# CV060_IO.net
KiCad netlist of a schematic drawn in Altium Designer
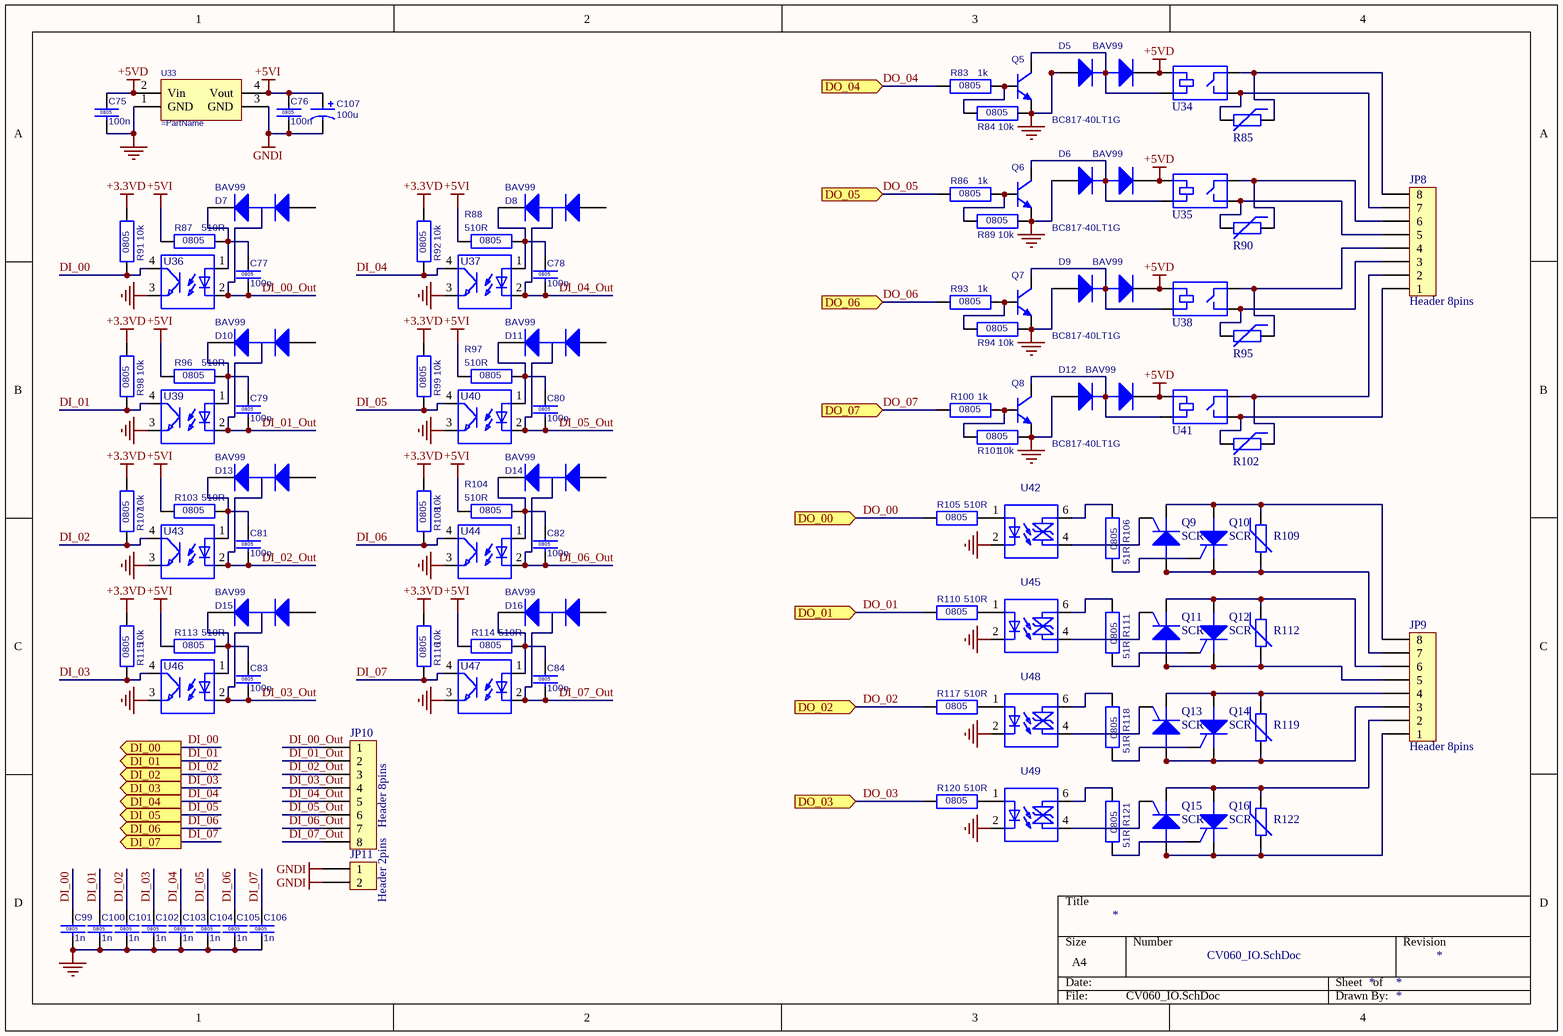
[diagram p0: CV060_IO.SchDoc]

(export (version "E")
  (design (tool "Eeschema 10.0.6"))
  (components
    (comp (ref "C75")
      (value "100n")
      (footprint "RC0805")
      (description "Chip capacitor, 20p")
      (fields
        (field (name "VOLTAGE") "50V")
        (field (name "MANUFACTURER") "KEMET, YAGEO")
        (field (name "CASE") "0805")
      )
      (libsource (lib "Aldiva_Altium_Library") (part "Capacitor_nonpolar_case"))
    )
    (comp (ref "C76")
      (value "100n")
      (footprint "RC0805")
      (description "Chip capacitor, 20p")
      (fields
        (field (name "VOLTAGE") "50V")
        (field (name "MANUFACTURER") "KEMET, YAGEO")
        (field (name "CASE") "0805")
      )
      (libsource (lib "Aldiva_Altium_Library") (part "Capacitor_nonpolar_case"))
    )
    (comp (ref "C77")
      (value "100n")
      (footprint "RC0805")
      (description "Chip capacitor, 20p")
      (fields
        (field (name "VOLTAGE") "50V")
        (field (name "MANUFACTURER") "KEMET, YAGEO")
        (field (name "CASE") "0805")
      )
      (libsource (lib "Aldiva_Altium_Library") (part "Capacitor_nonpolar_case"))
    )
    (comp (ref "C78")
      (value "100n")
      (footprint "RC0805")
      (description "Chip capacitor, 20p")
      (fields
        (field (name "VOLTAGE") "50V")
        (field (name "MANUFACTURER") "KEMET, YAGEO")
        (field (name "CASE") "0805")
      )
      (libsource (lib "Aldiva_Altium_Library") (part "Capacitor_nonpolar_case"))
    )
    (comp (ref "C79")
      (value "100n")
      (footprint "RC0805")
      (description "Chip capacitor, 20p")
      (fields
        (field (name "VOLTAGE") "50V")
        (field (name "MANUFACTURER") "KEMET, YAGEO")
        (field (name "CASE") "0805")
      )
      (libsource (lib "Aldiva_Altium_Library") (part "Capacitor_nonpolar_case"))
    )
    (comp (ref "C80")
      (value "100n")
      (footprint "RC0805")
      (description "Chip capacitor, 20p")
      (fields
        (field (name "VOLTAGE") "50V")
        (field (name "MANUFACTURER") "KEMET, YAGEO")
        (field (name "CASE") "0805")
      )
      (libsource (lib "Aldiva_Altium_Library") (part "Capacitor_nonpolar_case"))
    )
    (comp (ref "C81")
      (value "100n")
      (footprint "RC0805")
      (description "Chip capacitor, 20p")
      (fields
        (field (name "VOLTAGE") "50V")
        (field (name "MANUFACTURER") "KEMET, YAGEO")
        (field (name "CASE") "0805")
      )
      (libsource (lib "Aldiva_Altium_Library") (part "Capacitor_nonpolar_case"))
    )
    (comp (ref "C82")
      (value "100n")
      (footprint "RC0805")
      (description "Chip capacitor, 20p")
      (fields
        (field (name "VOLTAGE") "50V")
        (field (name "MANUFACTURER") "KEMET, YAGEO")
        (field (name "CASE") "0805")
      )
      (libsource (lib "Aldiva_Altium_Library") (part "Capacitor_nonpolar_case"))
    )
    (comp (ref "C83")
      (value "100n")
      (footprint "RC0805")
      (description "Chip capacitor, 20p")
      (fields
        (field (name "VOLTAGE") "50V")
        (field (name "MANUFACTURER") "KEMET, YAGEO")
        (field (name "CASE") "0805")
      )
      (libsource (lib "Aldiva_Altium_Library") (part "Capacitor_nonpolar_case"))
    )
    (comp (ref "C84")
      (value "100n")
      (footprint "RC0805")
      (description "Chip capacitor, 20p")
      (fields
        (field (name "VOLTAGE") "50V")
        (field (name "MANUFACTURER") "KEMET, YAGEO")
        (field (name "CASE") "0805")
      )
      (libsource (lib "Aldiva_Altium_Library") (part "Capacitor_nonpolar_case"))
    )
    (comp (ref "C99")
      (value "1n")
      (footprint "RC0805")
      (description "Chip capacitor, 20p")
      (fields
        (field (name "VOLTAGE") "50V")
        (field (name "MANUFACTURER") "KEMET, YAGEO")
        (field (name "CASE") "0805")
      )
      (libsource (lib "Aldiva_Altium_Library") (part "Capacitor_nonpolar_case"))
    )
    (comp (ref "C100")
      (value "1n")
      (footprint "RC0805")
      (description "Chip capacitor, 20p")
      (fields
        (field (name "VOLTAGE") "50V")
        (field (name "MANUFACTURER") "KEMET, YAGEO")
        (field (name "CASE") "0805")
      )
      (libsource (lib "Aldiva_Altium_Library") (part "Capacitor_nonpolar_case"))
    )
    (comp (ref "C101")
      (value "1n")
      (footprint "RC0805")
      (description "Chip capacitor, 20p")
      (fields
        (field (name "VOLTAGE") "50V")
        (field (name "MANUFACTURER") "KEMET, YAGEO")
        (field (name "CASE") "0805")
      )
      (libsource (lib "Aldiva_Altium_Library") (part "Capacitor_nonpolar_case"))
    )
    (comp (ref "C102")
      (value "1n")
      (footprint "RC0805")
      (description "Chip capacitor, 20p")
      (fields
        (field (name "VOLTAGE") "50V")
        (field (name "MANUFACTURER") "KEMET, YAGEO")
        (field (name "CASE") "0805")
      )
      (libsource (lib "Aldiva_Altium_Library") (part "Capacitor_nonpolar_case"))
    )
    (comp (ref "C103")
      (value "1n")
      (footprint "RC0805")
      (description "Chip capacitor, 20p")
      (fields
        (field (name "VOLTAGE") "50V")
        (field (name "MANUFACTURER") "KEMET, YAGEO")
        (field (name "CASE") "0805")
      )
      (libsource (lib "Aldiva_Altium_Library") (part "Capacitor_nonpolar_case"))
    )
    (comp (ref "C104")
      (value "1n")
      (footprint "RC0805")
      (description "Chip capacitor, 20p")
      (fields
        (field (name "VOLTAGE") "50V")
        (field (name "MANUFACTURER") "KEMET, YAGEO")
        (field (name "CASE") "0805")
      )
      (libsource (lib "Aldiva_Altium_Library") (part "Capacitor_nonpolar_case"))
    )
    (comp (ref "C105")
      (value "1n")
      (footprint "RC0805")
      (description "Chip capacitor, 20p")
      (fields
        (field (name "VOLTAGE") "50V")
        (field (name "MANUFACTURER") "KEMET, YAGEO")
        (field (name "CASE") "0805")
      )
      (libsource (lib "Aldiva_Altium_Library") (part "Capacitor_nonpolar_case"))
    )
    (comp (ref "C106")
      (value "1n")
      (footprint "RC0805")
      (description "Chip capacitor, 20p")
      (fields
        (field (name "VOLTAGE") "50V")
        (field (name "MANUFACTURER") "KEMET, YAGEO")
        (field (name "CASE") "0805")
      )
      (libsource (lib "Aldiva_Altium_Library") (part "Capacitor_nonpolar_case"))
    )
    (comp (ref "C107")
      (value "100u")
      (footprint "CEH12.5D5P2.5")
      (description "Electrolytic capacitor")
      (fields (field (name "PART NUMBER") "CEH12.5D5P2.5M-16V-100U") (field (name "VOLTAGE") "16V"))
      (libsource (lib "Aldiva_Altium_Library") (part "Capacitor_polar"))
    )
    (comp (ref "D5")
      (value "BAV99")
      (footprint "SOT23-3")
      (description "Dual small signal diode")
      (fields
        (field (name "MANUFACTURER") "Fairchild")
        (field (name "PART NUMBER") "BAV99")
        (field (name "VOLTAGE") "70V")
      )
      (libsource (lib "Aldiva_Altium_Library") (part "BAV99"))
    )
    (comp (ref "D6")
      (value "BAV99")
      (footprint "SOT23-3")
      (description "Dual small signal diode")
      (fields
        (field (name "MANUFACTURER") "Fairchild")
        (field (name "PART NUMBER") "BAV99")
        (field (name "VOLTAGE") "70V")
      )
      (libsource (lib "Aldiva_Altium_Library") (part "BAV99"))
    )
    (comp (ref "D7")
      (value "BAV99")
      (footprint "SOT23-3")
      (description "Dual small signal diode")
      (fields
        (field (name "MANUFACTURER") "Fairchild")
        (field (name "PART NUMBER") "BAV99")
        (field (name "VOLTAGE") "70V")
      )
      (libsource (lib "Aldiva_Altium_Library") (part "BAV99"))
    )
    (comp (ref "D8")
      (value "BAV99")
      (footprint "SOT23-3")
      (description "Dual small signal diode")
      (fields
        (field (name "MANUFACTURER") "Fairchild")
        (field (name "PART NUMBER") "BAV99")
        (field (name "VOLTAGE") "70V")
      )
      (libsource (lib "Aldiva_Altium_Library") (part "BAV99"))
    )
    (comp (ref "D9")
      (value "BAV99")
      (footprint "SOT23-3")
      (description "Dual small signal diode")
      (fields
        (field (name "MANUFACTURER") "Fairchild")
        (field (name "PART NUMBER") "BAV99")
        (field (name "VOLTAGE") "70V")
      )
      (libsource (lib "Aldiva_Altium_Library") (part "BAV99"))
    )
    (comp (ref "D10")
      (value "BAV99")
      (footprint "SOT23-3")
      (description "Dual small signal diode")
      (fields
        (field (name "MANUFACTURER") "Fairchild")
        (field (name "PART NUMBER") "BAV99")
        (field (name "VOLTAGE") "70V")
      )
      (libsource (lib "Aldiva_Altium_Library") (part "BAV99"))
    )
    (comp (ref "D11")
      (value "BAV99")
      (footprint "SOT23-3")
      (description "Dual small signal diode")
      (fields
        (field (name "MANUFACTURER") "Fairchild")
        (field (name "PART NUMBER") "BAV99")
        (field (name "VOLTAGE") "70V")
      )
      (libsource (lib "Aldiva_Altium_Library") (part "BAV99"))
    )
    (comp (ref "D12")
      (value "BAV99")
      (footprint "SOT23-3")
      (description "Dual small signal diode")
      (fields
        (field (name "MANUFACTURER") "Fairchild")
        (field (name "PART NUMBER") "BAV99")
        (field (name "VOLTAGE") "70V")
      )
      (libsource (lib "Aldiva_Altium_Library") (part "BAV99"))
    )
    (comp (ref "D13")
      (value "BAV99")
      (footprint "SOT23-3")
      (description "Dual small signal diode")
      (fields
        (field (name "MANUFACTURER") "Fairchild")
        (field (name "PART NUMBER") "BAV99")
        (field (name "VOLTAGE") "70V")
      )
      (libsource (lib "Aldiva_Altium_Library") (part "BAV99"))
    )
    (comp (ref "D14")
      (value "BAV99")
      (footprint "SOT23-3")
      (description "Dual small signal diode")
      (fields
        (field (name "MANUFACTURER") "Fairchild")
        (field (name "PART NUMBER") "BAV99")
        (field (name "VOLTAGE") "70V")
      )
      (libsource (lib "Aldiva_Altium_Library") (part "BAV99"))
    )
    (comp (ref "D15")
      (value "BAV99")
      (footprint "SOT23-3")
      (description "Dual small signal diode")
      (fields
        (field (name "MANUFACTURER") "Fairchild")
        (field (name "PART NUMBER") "BAV99")
        (field (name "VOLTAGE") "70V")
      )
      (libsource (lib "Aldiva_Altium_Library") (part "BAV99"))
    )
    (comp (ref "D16")
      (value "BAV99")
      (footprint "SOT23-3")
      (description "Dual small signal diode")
      (fields
        (field (name "MANUFACTURER") "Fairchild")
        (field (name "PART NUMBER") "BAV99")
        (field (name "VOLTAGE") "70V")
      )
      (libsource (lib "Aldiva_Altium_Library") (part "BAV99"))
    )
    (comp (ref "JP8")
      (value "Header 8pins")
      (footprint "PHOENIX_5.08_8PINS")
      (description "5.08mm angled 8pins receptabe")
      (fields
        (field (name "PART NUMBER") "2EDGR-5.08-08P-14")
        (field (name "MANUFACTURER PART NUMBER") "2EDGR-5.0-08P-14")
      )
      (libsource (lib "Aldiva_Altium_Library") (part "Header 8pins"))
    )
    (comp (ref "JP9")
      (value "Header 8pins")
      (footprint "PHOENIX_5.08_8PINS")
      (description "5.08mm angled 8pins receptabe")
      (fields
        (field (name "PART NUMBER") "2EDGR-5.08-08P-14")
        (field (name "MANUFACTURER PART NUMBER") "2EDGR-5.0-08P-14")
      )
      (libsource (lib "Aldiva_Altium_Library") (part "Header 8pins"))
    )
    (comp (ref "JP10")
      (value "Header 8pins")
      (footprint "PHOENIX_5.08_8PINS")
      (description "5.08mm angled 8pins receptabe")
      (fields
        (field (name "PART NUMBER") "2EDGR-5.08-08P-14")
        (field (name "MANUFACTURER PART NUMBER") "2EDGR-5.0-08P-14")
      )
      (libsource (lib "") (part "Header 8pins_1"))
    )
    (comp (ref "JP11")
      (value "Header 2pins")
      (footprint "PHOENIX_5.08_2PINS")
      (description "5mm angled 2pins receptabe")
      (fields
        (field (name "PART NUMBER") "2EDGR-5.08-02P-14")
        (field (name "MANUFACTURER PART NUMBER") "2EDGR-5.0-02P-14")
      )
      (libsource (lib "Aldiva_Altium_Library") (part "Header 2pins"))
    )
    (comp (ref "Q5")
      (value "NPN_transistor_SOT23-3")
      (footprint "SOT23-3")
      (description "General Purpose  NPN Transistor")
      (fields
        (field (name "PART NUMBER") "BC817-40LT1G")
        (field (name "MANUFACTURER") "ONS, NXP")
        (field (name "MANUFACTURER PART NUMBER") "BC817?40LT1G")
      )
      (libsource (lib "Aldiva_Altium_Library") (part "NPN_transistor_SOT23-3"))
    )
    (comp (ref "Q6")
      (value "NPN_transistor_SOT23-3")
      (footprint "SOT23-3")
      (description "General Purpose  NPN Transistor")
      (fields
        (field (name "PART NUMBER") "BC817-40LT1G")
        (field (name "MANUFACTURER") "ONS, NXP")
        (field (name "MANUFACTURER PART NUMBER") "BC817?40LT1G")
      )
      (libsource (lib "Aldiva_Altium_Library") (part "NPN_transistor_SOT23-3"))
    )
    (comp (ref "Q7")
      (value "NPN_transistor_SOT23-3")
      (footprint "SOT23-3")
      (description "General Purpose  NPN Transistor")
      (fields
        (field (name "PART NUMBER") "BC817-40LT1G")
        (field (name "MANUFACTURER") "ONS, NXP")
        (field (name "MANUFACTURER PART NUMBER") "BC817?40LT1G")
      )
      (libsource (lib "Aldiva_Altium_Library") (part "NPN_transistor_SOT23-3"))
    )
    (comp (ref "Q8")
      (value "NPN_transistor_SOT23-3")
      (footprint "SOT23-3")
      (description "General Purpose  NPN Transistor")
      (fields
        (field (name "PART NUMBER") "BC817-40LT1G")
        (field (name "MANUFACTURER") "ONS, NXP")
        (field (name "MANUFACTURER PART NUMBER") "BC817?40LT1G")
      )
      (libsource (lib "Aldiva_Altium_Library") (part "NPN_transistor_SOT23-3"))
    )
    (comp (ref "Q9")
      (value "SCR")
      (footprint "TO-220AB_V")
      (description "Thyristor")
      (fields
        (field (name "PART NUMBER") "BT151-800_V")
        (field (name "MANUFACTURER PART NUMBER") "BT151-800")
      )
      (libsource (lib "Aldiva_Altium_Library") (part "SCR"))
    )
    (comp (ref "Q10")
      (value "SCR")
      (footprint "TO-220AB_V")
      (description "Thyristor")
      (fields
        (field (name "PART NUMBER") "BT151-800_V")
        (field (name "MANUFACTURER PART NUMBER") "BT151-800")
      )
      (libsource (lib "Aldiva_Altium_Library") (part "SCR"))
    )
    (comp (ref "Q11")
      (value "SCR")
      (footprint "TO-220AB_V")
      (description "Thyristor")
      (fields
        (field (name "PART NUMBER") "BT151-800_V")
        (field (name "MANUFACTURER PART NUMBER") "BT151-800")
      )
      (libsource (lib "Aldiva_Altium_Library") (part "SCR"))
    )
    (comp (ref "Q12")
      (value "SCR")
      (footprint "TO-220AB_V")
      (description "Thyristor")
      (fields
        (field (name "PART NUMBER") "BT151-800_V")
        (field (name "MANUFACTURER PART NUMBER") "BT151-800")
      )
      (libsource (lib "Aldiva_Altium_Library") (part "SCR"))
    )
    (comp (ref "Q13")
      (value "SCR")
      (footprint "TO-220AB_V")
      (description "Thyristor")
      (fields
        (field (name "PART NUMBER") "BT151-800_V")
        (field (name "MANUFACTURER PART NUMBER") "BT151-800")
      )
      (libsource (lib "Aldiva_Altium_Library") (part "SCR"))
    )
    (comp (ref "Q14")
      (value "SCR")
      (footprint "TO-220AB_V")
      (description "Thyristor")
      (fields
        (field (name "PART NUMBER") "BT151-800_V")
        (field (name "MANUFACTURER PART NUMBER") "BT151-800")
      )
      (libsource (lib "Aldiva_Altium_Library") (part "SCR"))
    )
    (comp (ref "Q15")
      (value "SCR")
      (footprint "TO-220AB_V")
      (description "Thyristor")
      (fields
        (field (name "PART NUMBER") "BT151-800_V")
        (field (name "MANUFACTURER PART NUMBER") "BT151-800")
      )
      (libsource (lib "Aldiva_Altium_Library") (part "SCR"))
    )
    (comp (ref "Q16")
      (value "SCR")
      (footprint "TO-220AB_V")
      (description "Thyristor")
      (fields
        (field (name "PART NUMBER") "BT151-800_V")
        (field (name "MANUFACTURER PART NUMBER") "BT151-800")
      )
      (libsource (lib "Aldiva_Altium_Library") (part "SCR"))
    )
    (comp (ref "R83")
      (value "1k")
      (footprint "RC0805")
      (description "Chip resistor")
      (fields
        (field (name "CASE") "0805")
        (field (name "PART NUMBER") "RC0805F-1K00")
        (field (name "VOLTAGE") "200V")
      )
      (libsource (lib "Aldiva_Altium_Library") (part "Resistor"))
    )
    (comp (ref "R84")
      (value "10k")
      (footprint "RC0805")
      (description "Chip resistor")
      (fields
        (field (name "CASE") "0805")
        (field (name "PART NUMBER") "RC0805F-10K0")
        (field (name "VOLTAGE") "200V")
      )
      (libsource (lib "Aldiva_Altium_Library") (part "Resistor"))
    )
    (comp (ref "R85")
      (value "Varistor")
      (footprint "ROV07")
      (fields
        (field (name "PART NUMBER") "ROV07-391K")
        (field (name "VOLTAGE") "250AC")
        (field (name "MANUFACTURER") "Raychem")
      )
      (libsource (lib "Aldiva_Altium_Library") (part "Varistor"))
    )
    (comp (ref "R86")
      (value "1k")
      (footprint "RC0805")
      (description "Chip resistor")
      (fields
        (field (name "CASE") "0805")
        (field (name "PART NUMBER") "RC0805F-1K00")
        (field (name "VOLTAGE") "200V")
      )
      (libsource (lib "Aldiva_Altium_Library") (part "Resistor"))
    )
    (comp (ref "R87")
      (value "510R")
      (footprint "RC0805")
      (description "Chip resistor")
      (fields
        (field (name "CASE") "0805")
        (field (name "PART NUMBER") "RC0805F-510R")
        (field (name "VOLTAGE") "200V")
      )
      (libsource (lib "Aldiva_Altium_Library") (part "Resistor"))
    )
    (comp (ref "R88")
      (value "510R")
      (footprint "RC0805")
      (description "Chip resistor")
      (fields
        (field (name "CASE") "0805")
        (field (name "PART NUMBER") "RC0805F-510R")
        (field (name "VOLTAGE") "200V")
      )
      (libsource (lib "Aldiva_Altium_Library") (part "Resistor"))
    )
    (comp (ref "R89")
      (value "10k")
      (footprint "RC0805")
      (description "Chip resistor")
      (fields
        (field (name "CASE") "0805")
        (field (name "PART NUMBER") "RC0805F-10K0")
        (field (name "VOLTAGE") "200V")
      )
      (libsource (lib "Aldiva_Altium_Library") (part "Resistor"))
    )
    (comp (ref "R90")
      (value "Varistor")
      (footprint "ROV07")
      (fields
        (field (name "PART NUMBER") "ROV07-391K")
        (field (name "VOLTAGE") "250AC")
        (field (name "MANUFACTURER") "Raychem")
      )
      (libsource (lib "Aldiva_Altium_Library") (part "Varistor"))
    )
    (comp (ref "R91")
      (value "10k")
      (footprint "RC0805")
      (description "Chip resistor")
      (fields
        (field (name "CASE") "0805")
        (field (name "PART NUMBER") "RC0805F-10K0")
        (field (name "VOLTAGE") "200V")
      )
      (libsource (lib "Aldiva_Altium_Library") (part "Resistor"))
    )
    (comp (ref "R92")
      (value "10k")
      (footprint "RC0805")
      (description "Chip resistor")
      (fields
        (field (name "CASE") "0805")
        (field (name "PART NUMBER") "RC0805F-10K0")
        (field (name "VOLTAGE") "200V")
      )
      (libsource (lib "Aldiva_Altium_Library") (part "Resistor"))
    )
    (comp (ref "R93")
      (value "1k")
      (footprint "RC0805")
      (description "Chip resistor")
      (fields
        (field (name "CASE") "0805")
        (field (name "PART NUMBER") "RC0805F-1K00")
        (field (name "VOLTAGE") "200V")
      )
      (libsource (lib "Aldiva_Altium_Library") (part "Resistor"))
    )
    (comp (ref "R94")
      (value "10k")
      (footprint "RC0805")
      (description "Chip resistor")
      (fields
        (field (name "CASE") "0805")
        (field (name "PART NUMBER") "RC0805F-10K0")
        (field (name "VOLTAGE") "200V")
      )
      (libsource (lib "Aldiva_Altium_Library") (part "Resistor"))
    )
    (comp (ref "R95")
      (value "Varistor")
      (footprint "ROV07")
      (fields
        (field (name "PART NUMBER") "ROV07-391K")
        (field (name "VOLTAGE") "250AC")
        (field (name "MANUFACTURER") "Raychem")
      )
      (libsource (lib "Aldiva_Altium_Library") (part "Varistor"))
    )
    (comp (ref "R96")
      (value "510R")
      (footprint "RC0805")
      (description "Chip resistor")
      (fields
        (field (name "CASE") "0805")
        (field (name "PART NUMBER") "RC0805F-510R")
        (field (name "VOLTAGE") "200V")
      )
      (libsource (lib "Aldiva_Altium_Library") (part "Resistor"))
    )
    (comp (ref "R97")
      (value "510R")
      (footprint "RC0805")
      (description "Chip resistor")
      (fields
        (field (name "CASE") "0805")
        (field (name "PART NUMBER") "RC0805F-510R")
        (field (name "VOLTAGE") "200V")
      )
      (libsource (lib "Aldiva_Altium_Library") (part "Resistor"))
    )
    (comp (ref "R98")
      (value "10k")
      (footprint "RC0805")
      (description "Chip resistor")
      (fields
        (field (name "CASE") "0805")
        (field (name "PART NUMBER") "RC0805F-10K0")
        (field (name "VOLTAGE") "200V")
      )
      (libsource (lib "Aldiva_Altium_Library") (part "Resistor"))
    )
    (comp (ref "R99")
      (value "10k")
      (footprint "RC0805")
      (description "Chip resistor")
      (fields
        (field (name "CASE") "0805")
        (field (name "PART NUMBER") "RC0805F-10K0")
        (field (name "VOLTAGE") "200V")
      )
      (libsource (lib "Aldiva_Altium_Library") (part "Resistor"))
    )
    (comp (ref "R100")
      (value "1k")
      (footprint "RC0805")
      (description "Chip resistor")
      (fields
        (field (name "CASE") "0805")
        (field (name "PART NUMBER") "RC0805F-1K00")
        (field (name "VOLTAGE") "200V")
      )
      (libsource (lib "Aldiva_Altium_Library") (part "Resistor"))
    )
    (comp (ref "R101")
      (value "10k")
      (footprint "RC0805")
      (description "Chip resistor")
      (fields
        (field (name "CASE") "0805")
        (field (name "PART NUMBER") "RC0805F-10K0")
        (field (name "VOLTAGE") "200V")
      )
      (libsource (lib "Aldiva_Altium_Library") (part "Resistor"))
    )
    (comp (ref "R102")
      (value "Varistor")
      (footprint "ROV07")
      (fields
        (field (name "PART NUMBER") "ROV07-391K")
        (field (name "VOLTAGE") "250AC")
        (field (name "MANUFACTURER") "Raychem")
      )
      (libsource (lib "Aldiva_Altium_Library") (part "Varistor"))
    )
    (comp (ref "R103")
      (value "510R")
      (footprint "RC0805")
      (description "Chip resistor")
      (fields
        (field (name "CASE") "0805")
        (field (name "PART NUMBER") "RC0805F-510R")
        (field (name "VOLTAGE") "200V")
      )
      (libsource (lib "Aldiva_Altium_Library") (part "Resistor"))
    )
    (comp (ref "R104")
      (value "510R")
      (footprint "RC0805")
      (description "Chip resistor")
      (fields
        (field (name "CASE") "0805")
        (field (name "PART NUMBER") "RC0805F-510R")
        (field (name "VOLTAGE") "200V")
      )
      (libsource (lib "Aldiva_Altium_Library") (part "Resistor"))
    )
    (comp (ref "R105")
      (value "510R")
      (footprint "RC0805")
      (description "Chip resistor")
      (fields
        (field (name "CASE") "0805")
        (field (name "PART NUMBER") "RC0805F-510R")
        (field (name "VOLTAGE") "200V")
      )
      (libsource (lib "Aldiva_Altium_Library") (part "Resistor"))
    )
    (comp (ref "R106")
      (value "51R")
      (footprint "RC0805")
      (description "Chip resistor")
      (fields
        (field (name "CASE") "0805")
        (field (name "PART NUMBER") "RC0805F-51R0")
        (field (name "VOLTAGE") "200V")
      )
      (libsource (lib "Aldiva_Altium_Library") (part "Resistor"))
    )
    (comp (ref "R107")
      (value "10k")
      (footprint "RC0805")
      (description "Chip resistor")
      (fields
        (field (name "CASE") "0805")
        (field (name "PART NUMBER") "RC0805F-10K0")
        (field (name "VOLTAGE") "200V")
      )
      (libsource (lib "Aldiva_Altium_Library") (part "Resistor"))
    )
    (comp (ref "R108")
      (value "10k")
      (footprint "RC0805")
      (description "Chip resistor")
      (fields
        (field (name "CASE") "0805")
        (field (name "PART NUMBER") "RC0805F-10K0")
        (field (name "VOLTAGE") "200V")
      )
      (libsource (lib "Aldiva_Altium_Library") (part "Resistor"))
    )
    (comp (ref "R109")
      (value "Varistor")
      (footprint "ROV07")
      (fields
        (field (name "PART NUMBER") "ROV07-391K")
        (field (name "VOLTAGE") "250AC")
        (field (name "MANUFACTURER") "Raychem")
      )
      (libsource (lib "Aldiva_Altium_Library") (part "Varistor"))
    )
    (comp (ref "R110")
      (value "510R")
      (footprint "RC0805")
      (description "Chip resistor")
      (fields
        (field (name "CASE") "0805")
        (field (name "PART NUMBER") "RC0805F-510R")
        (field (name "VOLTAGE") "200V")
      )
      (libsource (lib "Aldiva_Altium_Library") (part "Resistor"))
    )
    (comp (ref "R111")
      (value "51R")
      (footprint "RC0805")
      (description "Chip resistor")
      (fields
        (field (name "CASE") "0805")
        (field (name "PART NUMBER") "RC0805F-51R0")
        (field (name "VOLTAGE") "200V")
      )
      (libsource (lib "Aldiva_Altium_Library") (part "Resistor"))
    )
    (comp (ref "R112")
      (value "Varistor")
      (footprint "ROV07")
      (fields
        (field (name "PART NUMBER") "ROV07-391K")
        (field (name "VOLTAGE") "250AC")
        (field (name "MANUFACTURER") "Raychem")
      )
      (libsource (lib "Aldiva_Altium_Library") (part "Varistor"))
    )
    (comp (ref "R113")
      (value "510R")
      (footprint "RC0805")
      (description "Chip resistor")
      (fields
        (field (name "CASE") "0805")
        (field (name "PART NUMBER") "RC0805F-510R")
        (field (name "VOLTAGE") "200V")
      )
      (libsource (lib "Aldiva_Altium_Library") (part "Resistor"))
    )
    (comp (ref "R114")
      (value "510R")
      (footprint "RC0805")
      (description "Chip resistor")
      (fields
        (field (name "CASE") "0805")
        (field (name "PART NUMBER") "RC0805F-510R")
        (field (name "VOLTAGE") "200V")
      )
      (libsource (lib "Aldiva_Altium_Library") (part "Resistor"))
    )
    (comp (ref "R115")
      (value "10k")
      (footprint "RC0805")
      (description "Chip resistor")
      (fields
        (field (name "CASE") "0805")
        (field (name "PART NUMBER") "RC0805F-10K0")
        (field (name "VOLTAGE") "200V")
      )
      (libsource (lib "Aldiva_Altium_Library") (part "Resistor"))
    )
    (comp (ref "R116")
      (value "10k")
      (footprint "RC0805")
      (description "Chip resistor")
      (fields
        (field (name "CASE") "0805")
        (field (name "PART NUMBER") "RC0805F-10K0")
        (field (name "VOLTAGE") "200V")
      )
      (libsource (lib "Aldiva_Altium_Library") (part "Resistor"))
    )
    (comp (ref "R117")
      (value "510R")
      (footprint "RC0805")
      (description "Chip resistor")
      (fields
        (field (name "CASE") "0805")
        (field (name "PART NUMBER") "RC0805F-510R")
        (field (name "VOLTAGE") "200V")
      )
      (libsource (lib "Aldiva_Altium_Library") (part "Resistor"))
    )
    (comp (ref "R118")
      (value "51R")
      (footprint "RC0805")
      (description "Chip resistor")
      (fields
        (field (name "CASE") "0805")
        (field (name "PART NUMBER") "RC0805F-51R0")
        (field (name "VOLTAGE") "200V")
      )
      (libsource (lib "Aldiva_Altium_Library") (part "Resistor"))
    )
    (comp (ref "R119")
      (value "Varistor")
      (footprint "ROV07")
      (fields
        (field (name "PART NUMBER") "ROV07-391K")
        (field (name "VOLTAGE") "250AC")
        (field (name "MANUFACTURER") "Raychem")
      )
      (libsource (lib "Aldiva_Altium_Library") (part "Varistor"))
    )
    (comp (ref "R120")
      (value "510R")
      (footprint "RC0805")
      (description "Chip resistor")
      (fields
        (field (name "CASE") "0805")
        (field (name "PART NUMBER") "RC0805F-510R")
        (field (name "VOLTAGE") "200V")
      )
      (libsource (lib "Aldiva_Altium_Library") (part "Resistor"))
    )
    (comp (ref "R121")
      (value "51R")
      (footprint "RC0805")
      (description "Chip resistor")
      (fields
        (field (name "CASE") "0805")
        (field (name "PART NUMBER") "RC0805F-51R0")
        (field (name "VOLTAGE") "200V")
      )
      (libsource (lib "Aldiva_Altium_Library") (part "Resistor"))
    )
    (comp (ref "R122")
      (value "Varistor")
      (footprint "ROV07")
      (fields
        (field (name "PART NUMBER") "ROV07-391K")
        (field (name "VOLTAGE") "250AC")
        (field (name "MANUFACTURER") "Raychem")
      )
      (libsource (lib "Aldiva_Altium_Library") (part "Varistor"))
    )
    (comp (ref "U33")
      (value "~")
      (footprint "SIP4")
      (description "1W Insulated DCDC converter")
      (fields (field (name "PART NUMBER") "1-05-05S") (field (name "MANUFACTURER") "TI"))
      (libsource (lib "Aldiva_Altium_Library") (part "DCDC"))
    )
    (comp (ref "U34")
      (value "NPA-AS5-DC5V")
      (footprint "NPA-AS5-DC5V")
      (description "Standard")
      (libsource (lib "Aldiva_Altium_Library") (part "NPA-AS5-DC5V"))
    )
    (comp (ref "U35")
      (value "NPA-AS5-DC5V")
      (footprint "NPA-AS5-DC5V")
      (description "Standard")
      (libsource (lib "Aldiva_Altium_Library") (part "NPA-AS5-DC5V"))
    )
    (comp (ref "U36")
      (value "PC817")
      (footprint "DIP4")
      (description "General purpose optocouple")
      (fields (field (name "PART NUMBER") "PC817C") (field (name "MANUFACTURER") "Sharp"))
      (libsource (lib "Aldiva_Altium_Library") (part "PC817C"))
    )
    (comp (ref "U37")
      (value "PC817")
      (footprint "DIP4")
      (description "General purpose optocouple")
      (fields (field (name "PART NUMBER") "PC817C") (field (name "MANUFACTURER") "Sharp"))
      (libsource (lib "Aldiva_Altium_Library") (part "PC817C"))
    )
    (comp (ref "U38")
      (value "NPA-AS5-DC5V")
      (footprint "NPA-AS5-DC5V")
      (description "Standard")
      (libsource (lib "Aldiva_Altium_Library") (part "NPA-AS5-DC5V"))
    )
    (comp (ref "U39")
      (value "PC817")
      (footprint "DIP4")
      (description "General purpose optocouple")
      (fields (field (name "PART NUMBER") "PC817C") (field (name "MANUFACTURER") "Sharp"))
      (libsource (lib "Aldiva_Altium_Library") (part "PC817C"))
    )
    (comp (ref "U40")
      (value "PC817")
      (footprint "DIP4")
      (description "General purpose optocouple")
      (fields (field (name "PART NUMBER") "PC817C") (field (name "MANUFACTURER") "Sharp"))
      (libsource (lib "Aldiva_Altium_Library") (part "PC817C"))
    )
    (comp (ref "U41")
      (value "NPA-AS5-DC5V")
      (footprint "NPA-AS5-DC5V")
      (description "Standard")
      (libsource (lib "Aldiva_Altium_Library") (part "NPA-AS5-DC5V"))
    )
    (comp (ref "U42")
      (value "MOC3063")
      (footprint "DIP6")
      (description "Zero-Cross Phototriac Driver Optocoupler")
      (fields (field (name "MANUFACTURER") "Fairchild"))
      (libsource (lib "Aldiva_Altium_Library") (part "MOC3063"))
    )
    (comp (ref "U43")
      (value "PC817")
      (footprint "DIP4")
      (description "General purpose optocouple")
      (fields (field (name "PART NUMBER") "PC817C") (field (name "MANUFACTURER") "Sharp"))
      (libsource (lib "Aldiva_Altium_Library") (part "PC817C"))
    )
    (comp (ref "U44")
      (value "PC817")
      (footprint "DIP4")
      (description "General purpose optocouple")
      (fields (field (name "PART NUMBER") "PC817C") (field (name "MANUFACTURER") "Sharp"))
      (libsource (lib "Aldiva_Altium_Library") (part "PC817C"))
    )
    (comp (ref "U45")
      (value "MOC3063")
      (footprint "DIP6")
      (description "Zero-Cross Phototriac Driver Optocoupler")
      (fields (field (name "MANUFACTURER") "Fairchild"))
      (libsource (lib "Aldiva_Altium_Library") (part "MOC3063"))
    )
    (comp (ref "U46")
      (value "PC817")
      (footprint "DIP4")
      (description "General purpose optocouple")
      (fields (field (name "PART NUMBER") "PC817C") (field (name "MANUFACTURER") "Sharp"))
      (libsource (lib "Aldiva_Altium_Library") (part "PC817C"))
    )
    (comp (ref "U47")
      (value "PC817")
      (footprint "DIP4")
      (description "General purpose optocouple")
      (fields (field (name "PART NUMBER") "PC817C") (field (name "MANUFACTURER") "Sharp"))
      (libsource (lib "Aldiva_Altium_Library") (part "PC817C"))
    )
    (comp (ref "U48")
      (value "MOC3063")
      (footprint "DIP6")
      (description "Zero-Cross Phototriac Driver Optocoupler")
      (fields (field (name "MANUFACTURER") "Fairchild"))
      (libsource (lib "Aldiva_Altium_Library") (part "MOC3063"))
    )
    (comp (ref "U49")
      (value "MOC3063")
      (footprint "DIP6")
      (description "Zero-Cross Phototriac Driver Optocoupler")
      (fields (field (name "MANUFACTURER") "Fairchild"))
      (libsource (lib "Aldiva_Altium_Library") (part "MOC3063"))
    )
  )
  (nets
    (net (code "1") (name "+3.3VD") (class "Default")
      (node (ref "R107") (pin "2") (pinfunction "2_2") (pintype "passive"))
      (node (ref "R108") (pin "2") (pinfunction "2_2") (pintype "passive"))
      (node (ref "R115") (pin "2") (pinfunction "2_2") (pintype "passive"))
      (node (ref "R116") (pin "2") (pinfunction "2_2") (pintype "passive"))
      (node (ref "R91") (pin "2") (pinfunction "2_2") (pintype "passive"))
      (node (ref "R92") (pin "2") (pinfunction "2_2") (pintype "passive"))
      (node (ref "R98") (pin "2") (pinfunction "2_2") (pintype "passive"))
      (node (ref "R99") (pin "2") (pinfunction "2_2") (pintype "passive"))
    )
    (net (code "2") (name "+5VD") (class "Default")
      (node (ref "C75") (pin "1") (pinfunction "1_1") (pintype "passive"))
      (node (ref "D12") (pin "2") (pinfunction "K_2") (pintype "passive"))
      (node (ref "D5") (pin "2") (pinfunction "K_2") (pintype "passive"))
      (node (ref "D6") (pin "2") (pinfunction "K_2") (pintype "passive"))
      (node (ref "D9") (pin "2") (pinfunction "K_2") (pintype "passive"))
      (node (ref "U33") (pin "2") (pinfunction "Vin_2") (pintype "passive"))
      (node (ref "U34") (pin "1") (pinfunction "1_1") (pintype "passive"))
      (node (ref "U35") (pin "1") (pinfunction "1_1") (pintype "passive"))
      (node (ref "U38") (pin "1") (pinfunction "1_1") (pintype "passive"))
      (node (ref "U41") (pin "1") (pinfunction "1_1") (pintype "passive"))
    )
    (net (code "3") (name "+5VI") (class "Default")
      (node (ref "C107") (pin "1") (pinfunction "1_1") (pintype "passive"))
      (node (ref "C76") (pin "1") (pinfunction "1_1") (pintype "passive"))
      (node (ref "R103") (pin "1") (pinfunction "1_1") (pintype "passive"))
      (node (ref "R104") (pin "1") (pinfunction "1_1") (pintype "passive"))
      (node (ref "R113") (pin "1") (pinfunction "1_1") (pintype "passive"))
      (node (ref "R114") (pin "1") (pinfunction "1_1") (pintype "passive"))
      (node (ref "R87") (pin "1") (pinfunction "1_1") (pintype "passive"))
      (node (ref "R88") (pin "1") (pinfunction "1_1") (pintype "passive"))
      (node (ref "R96") (pin "1") (pinfunction "1_1") (pintype "passive"))
      (node (ref "R97") (pin "1") (pinfunction "1_1") (pintype "passive"))
      (node (ref "U33") (pin "4") (pinfunction "Vout_4") (pintype "passive"))
    )
    (net (code "4") (name "/DI_00") (class "Default")
      (node (ref "C99") (pin "1") (pinfunction "1_1") (pintype "passive"))
      (node (ref "R91") (pin "1") (pinfunction "1_1") (pintype "passive"))
      (node (ref "U36") (pin "4") (pintype "passive"))
    )
    (net (code "5") (name "/DI_00_Out") (class "Default")
      (node (ref "C77") (pin "2") (pinfunction "2_2") (pintype "passive"))
      (node (ref "D7") (pin "3") (pinfunction "C_3") (pintype "passive"))
      (node (ref "JP10") (pin "1") (pinfunction "1_1") (pintype "passive"))
      (node (ref "U36") (pin "2") (pintype "passive"))
    )
    (net (code "6") (name "/DI_01") (class "Default")
      (node (ref "C100") (pin "1") (pinfunction "1_1") (pintype "passive"))
      (node (ref "R98") (pin "1") (pinfunction "1_1") (pintype "passive"))
      (node (ref "U39") (pin "4") (pintype "passive"))
    )
    (net (code "7") (name "/DI_01_Out") (class "Default")
      (node (ref "C79") (pin "2") (pinfunction "2_2") (pintype "passive"))
      (node (ref "D10") (pin "3") (pinfunction "C_3") (pintype "passive"))
      (node (ref "JP10") (pin "2") (pinfunction "2_2") (pintype "passive"))
      (node (ref "U39") (pin "2") (pintype "passive"))
    )
    (net (code "8") (name "/DI_02") (class "Default")
      (node (ref "C101") (pin "1") (pinfunction "1_1") (pintype "passive"))
      (node (ref "R107") (pin "1") (pinfunction "1_1") (pintype "passive"))
      (node (ref "U43") (pin "4") (pintype "passive"))
    )
    (net (code "9") (name "/DI_02_Out") (class "Default")
      (node (ref "C81") (pin "2") (pinfunction "2_2") (pintype "passive"))
      (node (ref "D13") (pin "3") (pinfunction "C_3") (pintype "passive"))
      (node (ref "JP10") (pin "3") (pinfunction "3_3") (pintype "passive"))
      (node (ref "U43") (pin "2") (pintype "passive"))
    )
    (net (code "10") (name "/DI_03") (class "Default")
      (node (ref "C102") (pin "1") (pinfunction "1_1") (pintype "passive"))
      (node (ref "R115") (pin "1") (pinfunction "1_1") (pintype "passive"))
      (node (ref "U46") (pin "4") (pintype "passive"))
    )
    (net (code "11") (name "/DI_03_Out") (class "Default")
      (node (ref "C83") (pin "2") (pinfunction "2_2") (pintype "passive"))
      (node (ref "D15") (pin "3") (pinfunction "C_3") (pintype "passive"))
      (node (ref "JP10") (pin "4") (pinfunction "4_4") (pintype "passive"))
      (node (ref "U46") (pin "2") (pintype "passive"))
    )
    (net (code "12") (name "/DI_04") (class "Default")
      (node (ref "C103") (pin "1") (pinfunction "1_1") (pintype "passive"))
      (node (ref "R92") (pin "1") (pinfunction "1_1") (pintype "passive"))
      (node (ref "U37") (pin "4") (pintype "passive"))
    )
    (net (code "13") (name "/DI_04_Out") (class "Default")
      (node (ref "C78") (pin "2") (pinfunction "2_2") (pintype "passive"))
      (node (ref "D8") (pin "3") (pinfunction "C_3") (pintype "passive"))
      (node (ref "JP10") (pin "5") (pinfunction "5_5") (pintype "passive"))
      (node (ref "U37") (pin "2") (pintype "passive"))
    )
    (net (code "14") (name "/DI_05") (class "Default")
      (node (ref "C104") (pin "1") (pinfunction "1_1") (pintype "passive"))
      (node (ref "R99") (pin "1") (pinfunction "1_1") (pintype "passive"))
      (node (ref "U40") (pin "4") (pintype "passive"))
    )
    (net (code "15") (name "/DI_05_Out") (class "Default")
      (node (ref "C80") (pin "2") (pinfunction "2_2") (pintype "passive"))
      (node (ref "D11") (pin "3") (pinfunction "C_3") (pintype "passive"))
      (node (ref "JP10") (pin "6") (pinfunction "6_6") (pintype "passive"))
      (node (ref "U40") (pin "2") (pintype "passive"))
    )
    (net (code "16") (name "/DI_06") (class "Default")
      (node (ref "C105") (pin "1") (pinfunction "1_1") (pintype "passive"))
      (node (ref "R108") (pin "1") (pinfunction "1_1") (pintype "passive"))
      (node (ref "U44") (pin "4") (pintype "passive"))
    )
    (net (code "17") (name "/DI_06_Out") (class "Default")
      (node (ref "C82") (pin "2") (pinfunction "2_2") (pintype "passive"))
      (node (ref "D14") (pin "3") (pinfunction "C_3") (pintype "passive"))
      (node (ref "JP10") (pin "7") (pinfunction "7_7") (pintype "passive"))
      (node (ref "U44") (pin "2") (pintype "passive"))
    )
    (net (code "18") (name "/DI_07") (class "Default")
      (node (ref "C106") (pin "1") (pinfunction "1_1") (pintype "passive"))
      (node (ref "R116") (pin "1") (pinfunction "1_1") (pintype "passive"))
      (node (ref "U47") (pin "4") (pintype "passive"))
    )
    (net (code "19") (name "/DI_07_Out") (class "Default")
      (node (ref "C84") (pin "2") (pinfunction "2_2") (pintype "passive"))
      (node (ref "D16") (pin "3") (pinfunction "C_3") (pintype "passive"))
      (node (ref "JP10") (pin "8") (pinfunction "8_8") (pintype "passive"))
      (node (ref "U47") (pin "2") (pintype "passive"))
    )
    (net (code "20") (name "/DO_00") (class "Default")
      (node (ref "R105") (pin "1") (pinfunction "1_1") (pintype "passive"))
    )
    (net (code "21") (name "/DO_01") (class "Default")
      (node (ref "R110") (pin "1") (pinfunction "1_1") (pintype "passive"))
    )
    (net (code "22") (name "/DO_02") (class "Default")
      (node (ref "R117") (pin "1") (pinfunction "1_1") (pintype "passive"))
    )
    (net (code "23") (name "/DO_03") (class "Default")
      (node (ref "R120") (pin "1") (pinfunction "1_1") (pintype "passive"))
    )
    (net (code "24") (name "/DO_04") (class "Default")
      (node (ref "R83") (pin "1") (pinfunction "1_1") (pintype "passive"))
    )
    (net (code "25") (name "/DO_05") (class "Default")
      (node (ref "R86") (pin "1") (pinfunction "1_1") (pintype "passive"))
    )
    (net (code "26") (name "/DO_06") (class "Default")
      (node (ref "R93") (pin "1") (pinfunction "1_1") (pintype "passive"))
    )
    (net (code "27") (name "/DO_07") (class "Default")
      (node (ref "R100") (pin "1") (pinfunction "1_1") (pintype "passive"))
    )
    (net (code "28") (name "DGND") (class "Default")
      (node (ref "C100") (pin "2") (pinfunction "2_2") (pintype "passive"))
      (node (ref "C101") (pin "2") (pinfunction "2_2") (pintype "passive"))
      (node (ref "C102") (pin "2") (pinfunction "2_2") (pintype "passive"))
      (node (ref "C103") (pin "2") (pinfunction "2_2") (pintype "passive"))
      (node (ref "C104") (pin "2") (pinfunction "2_2") (pintype "passive"))
      (node (ref "C105") (pin "2") (pinfunction "2_2") (pintype "passive"))
      (node (ref "C106") (pin "2") (pinfunction "2_2") (pintype "passive"))
      (node (ref "C75") (pin "2") (pinfunction "2_2") (pintype "passive"))
      (node (ref "C99") (pin "2") (pinfunction "2_2") (pintype "passive"))
      (node (ref "D12") (pin "1") (pinfunction "A_1") (pintype "passive"))
      (node (ref "D5") (pin "1") (pinfunction "A_1") (pintype "passive"))
      (node (ref "D6") (pin "1") (pinfunction "A_1") (pintype "passive"))
      (node (ref "D9") (pin "1") (pinfunction "A_1") (pintype "passive"))
      (node (ref "Q5") (pin "2") (pinfunction "E_2") (pintype "passive"))
      (node (ref "Q6") (pin "2") (pinfunction "E_2") (pintype "passive"))
      (node (ref "Q7") (pin "2") (pinfunction "E_2") (pintype "passive"))
      (node (ref "Q8") (pin "2") (pinfunction "E_2") (pintype "passive"))
      (node (ref "R101") (pin "2") (pinfunction "2_2") (pintype "passive"))
      (node (ref "R84") (pin "2") (pinfunction "2_2") (pintype "passive"))
      (node (ref "R89") (pin "2") (pinfunction "2_2") (pintype "passive"))
      (node (ref "R94") (pin "2") (pinfunction "2_2") (pintype "passive"))
      (node (ref "U33") (pin "1") (pinfunction "GND_1") (pintype "passive"))
      (node (ref "U36") (pin "3") (pintype "passive"))
      (node (ref "U37") (pin "3") (pintype "passive"))
      (node (ref "U39") (pin "3") (pintype "passive"))
      (node (ref "U40") (pin "3") (pintype "passive"))
      (node (ref "U42") (pin "2") (pintype "passive"))
      (node (ref "U43") (pin "3") (pintype "passive"))
      (node (ref "U44") (pin "3") (pintype "passive"))
      (node (ref "U45") (pin "2") (pintype "passive"))
      (node (ref "U46") (pin "3") (pintype "passive"))
      (node (ref "U47") (pin "3") (pintype "passive"))
      (node (ref "U48") (pin "2") (pintype "passive"))
      (node (ref "U49") (pin "2") (pintype "passive"))
    )
    (net (code "29") (name "GNDI") (class "Default")
      (node (ref "C107") (pin "2") (pinfunction "2_2") (pintype "passive"))
      (node (ref "C76") (pin "2") (pinfunction "2_2") (pintype "passive"))
      (node (ref "JP11") (pin "1") (pinfunction "1_1") (pintype "passive"))
      (node (ref "JP11") (pin "2") (pinfunction "2_2") (pintype "passive"))
      (node (ref "U33") (pin "3") (pinfunction "GND_3") (pintype "passive"))
    )
    (net (code "30") (name "Net-(D5-C)") (class "Default")
      (node (ref "D5") (pin "3") (pinfunction "C_3") (pintype "passive"))
      (node (ref "Q5") (pin "3") (pinfunction "C_3") (pintype "passive"))
      (node (ref "U34") (pin "2") (pinfunction "2_2") (pintype "passive"))
    )
    (net (code "31") (name "Net-(D6-C)") (class "Default")
      (node (ref "D6") (pin "3") (pinfunction "C_3") (pintype "passive"))
      (node (ref "Q6") (pin "3") (pinfunction "C_3") (pintype "passive"))
      (node (ref "U35") (pin "2") (pinfunction "2_2") (pintype "passive"))
    )
    (net (code "32") (name "Net-(D7-K)") (class "Default")
      (node (ref "C77") (pin "1") (pinfunction "1_1") (pintype "passive"))
      (node (ref "D7") (pin "2") (pinfunction "K_2") (pintype "passive"))
      (node (ref "R87") (pin "2") (pinfunction "2_2") (pintype "passive"))
      (node (ref "U36") (pin "1") (pintype "passive"))
    )
    (net (code "33") (name "Net-(D8-K)") (class "Default")
      (node (ref "C78") (pin "1") (pinfunction "1_1") (pintype "passive"))
      (node (ref "D8") (pin "2") (pinfunction "K_2") (pintype "passive"))
      (node (ref "R88") (pin "2") (pinfunction "2_2") (pintype "passive"))
      (node (ref "U37") (pin "1") (pintype "passive"))
    )
    (net (code "34") (name "Net-(D9-C)") (class "Default")
      (node (ref "D9") (pin "3") (pinfunction "C_3") (pintype "passive"))
      (node (ref "Q7") (pin "3") (pinfunction "C_3") (pintype "passive"))
      (node (ref "U38") (pin "2") (pinfunction "2_2") (pintype "passive"))
    )
    (net (code "35") (name "Net-(D10-K)") (class "Default")
      (node (ref "C79") (pin "1") (pinfunction "1_1") (pintype "passive"))
      (node (ref "D10") (pin "2") (pinfunction "K_2") (pintype "passive"))
      (node (ref "R96") (pin "2") (pinfunction "2_2") (pintype "passive"))
      (node (ref "U39") (pin "1") (pintype "passive"))
    )
    (net (code "36") (name "Net-(D11-K)") (class "Default")
      (node (ref "C80") (pin "1") (pinfunction "1_1") (pintype "passive"))
      (node (ref "D11") (pin "2") (pinfunction "K_2") (pintype "passive"))
      (node (ref "R97") (pin "2") (pinfunction "2_2") (pintype "passive"))
      (node (ref "U40") (pin "1") (pintype "passive"))
    )
    (net (code "37") (name "Net-(D12-C)") (class "Default")
      (node (ref "D12") (pin "3") (pinfunction "C_3") (pintype "passive"))
      (node (ref "Q8") (pin "3") (pinfunction "C_3") (pintype "passive"))
      (node (ref "U41") (pin "2") (pinfunction "2_2") (pintype "passive"))
    )
    (net (code "38") (name "Net-(D13-K)") (class "Default")
      (node (ref "C81") (pin "1") (pinfunction "1_1") (pintype "passive"))
      (node (ref "D13") (pin "2") (pinfunction "K_2") (pintype "passive"))
      (node (ref "R103") (pin "2") (pinfunction "2_2") (pintype "passive"))
      (node (ref "U43") (pin "1") (pintype "passive"))
    )
    (net (code "39") (name "Net-(D14-K)") (class "Default")
      (node (ref "C82") (pin "1") (pinfunction "1_1") (pintype "passive"))
      (node (ref "D14") (pin "2") (pinfunction "K_2") (pintype "passive"))
      (node (ref "R104") (pin "2") (pinfunction "2_2") (pintype "passive"))
      (node (ref "U44") (pin "1") (pintype "passive"))
    )
    (net (code "40") (name "Net-(D15-K)") (class "Default")
      (node (ref "C83") (pin "1") (pinfunction "1_1") (pintype "passive"))
      (node (ref "D15") (pin "2") (pinfunction "K_2") (pintype "passive"))
      (node (ref "R113") (pin "2") (pinfunction "2_2") (pintype "passive"))
      (node (ref "U46") (pin "1") (pintype "passive"))
    )
    (net (code "41") (name "Net-(D16-K)") (class "Default")
      (node (ref "C84") (pin "1") (pinfunction "1_1") (pintype "passive"))
      (node (ref "D16") (pin "2") (pinfunction "K_2") (pintype "passive"))
      (node (ref "R114") (pin "2") (pinfunction "2_2") (pintype "passive"))
      (node (ref "U47") (pin "1") (pintype "passive"))
    )
    (net (code "42") (name "Net-(JP8-Pad1)") (class "Default")
      (node (ref "JP8") (pin "1") (pinfunction "1_1") (pintype "passive"))
      (node (ref "R102") (pin "2") (pinfunction "2_2") (pintype "passive"))
      (node (ref "U41") (pin "4") (pinfunction "4_4") (pintype "passive"))
    )
    (net (code "43") (name "Net-(JP8-Pad2)") (class "Default")
      (node (ref "JP8") (pin "2") (pinfunction "2_2") (pintype "passive"))
      (node (ref "R102") (pin "1") (pinfunction "1_1") (pintype "passive"))
      (node (ref "U41") (pin "3") (pinfunction "3_3") (pintype "passive"))
    )
    (net (code "44") (name "Net-(JP8-Pad3)") (class "Default")
      (node (ref "JP8") (pin "3") (pinfunction "3_3") (pintype "passive"))
      (node (ref "R95") (pin "2") (pinfunction "2_2") (pintype "passive"))
      (node (ref "U38") (pin "4") (pinfunction "4_4") (pintype "passive"))
    )
    (net (code "45") (name "Net-(JP8-Pad4)") (class "Default")
      (node (ref "JP8") (pin "4") (pinfunction "4_4") (pintype "passive"))
      (node (ref "R95") (pin "1") (pinfunction "1_1") (pintype "passive"))
      (node (ref "U38") (pin "3") (pinfunction "3_3") (pintype "passive"))
    )
    (net (code "46") (name "Net-(JP8-Pad5)") (class "Default")
      (node (ref "JP8") (pin "5") (pinfunction "5_5") (pintype "passive"))
      (node (ref "R90") (pin "2") (pinfunction "2_2") (pintype "passive"))
      (node (ref "U35") (pin "4") (pinfunction "4_4") (pintype "passive"))
    )
    (net (code "47") (name "Net-(JP8-Pad6)") (class "Default")
      (node (ref "JP8") (pin "6") (pinfunction "6_6") (pintype "passive"))
      (node (ref "R90") (pin "1") (pinfunction "1_1") (pintype "passive"))
      (node (ref "U35") (pin "3") (pinfunction "3_3") (pintype "passive"))
    )
    (net (code "48") (name "Net-(JP8-Pad7)") (class "Default")
      (node (ref "JP8") (pin "7") (pinfunction "7_7") (pintype "passive"))
      (node (ref "R85") (pin "2") (pinfunction "2_2") (pintype "passive"))
      (node (ref "U34") (pin "4") (pinfunction "4_4") (pintype "passive"))
    )
    (net (code "49") (name "Net-(JP8-Pad8)") (class "Default")
      (node (ref "JP8") (pin "8") (pinfunction "8_8") (pintype "passive"))
      (node (ref "R85") (pin "1") (pinfunction "1_1") (pintype "passive"))
      (node (ref "U34") (pin "3") (pinfunction "3_3") (pintype "passive"))
    )
    (net (code "50") (name "Net-(Q5-B)") (class "Default")
      (node (ref "Q5") (pin "1") (pinfunction "B_1") (pintype "passive"))
      (node (ref "R83") (pin "2") (pinfunction "2_2") (pintype "passive"))
      (node (ref "R84") (pin "1") (pinfunction "1_1") (pintype "passive"))
    )
    (net (code "51") (name "Net-(Q6-B)") (class "Default")
      (node (ref "Q6") (pin "1") (pinfunction "B_1") (pintype "passive"))
      (node (ref "R86") (pin "2") (pinfunction "2_2") (pintype "passive"))
      (node (ref "R89") (pin "1") (pinfunction "1_1") (pintype "passive"))
    )
    (net (code "52") (name "Net-(Q7-B)") (class "Default")
      (node (ref "Q7") (pin "1") (pinfunction "B_1") (pintype "passive"))
      (node (ref "R93") (pin "2") (pinfunction "2_2") (pintype "passive"))
      (node (ref "R94") (pin "1") (pinfunction "1_1") (pintype "passive"))
    )
    (net (code "53") (name "Net-(Q8-B)") (class "Default")
      (node (ref "Q8") (pin "1") (pinfunction "B_1") (pintype "passive"))
      (node (ref "R100") (pin "2") (pinfunction "2_2") (pintype "passive"))
      (node (ref "R101") (pin "1") (pinfunction "1_1") (pintype "passive"))
    )
    (net (code "54") (name "Net-(Q9-G)") (class "Default")
      (node (ref "Q9") (pin "3") (pinfunction "G_3") (pintype "passive"))
      (node (ref "U42") (pin "4") (pintype "passive"))
    )
    (net (code "55") (name "Net-(Q10-A)") (class "Default")
      (node (ref "JP9") (pin "8") (pinfunction "8_8") (pintype "passive"))
      (node (ref "Q10") (pin "2") (pinfunction "A_2") (pintype "passive"))
      (node (ref "Q10") (pin "4") (pinfunction "TAB_4") (pintype "passive"))
      (node (ref "Q9") (pin "1") (pinfunction "K_1") (pintype "passive"))
      (node (ref "R109") (pin "1") (pinfunction "1_1") (pintype "passive"))
    )
    (net (code "56") (name "Net-(Q10-G)") (class "Default")
      (node (ref "Q10") (pin "3") (pinfunction "G_3") (pintype "passive"))
      (node (ref "R106") (pin "2") (pinfunction "2_2") (pintype "passive"))
    )
    (net (code "57") (name "Net-(Q10-K)") (class "Default")
      (node (ref "JP9") (pin "7") (pinfunction "7_7") (pintype "passive"))
      (node (ref "Q10") (pin "1") (pinfunction "K_1") (pintype "passive"))
      (node (ref "Q9") (pin "2") (pinfunction "A_2") (pintype "passive"))
      (node (ref "Q9") (pin "4") (pinfunction "TAB_4") (pintype "passive"))
      (node (ref "R109") (pin "2") (pinfunction "2_2") (pintype "passive"))
    )
    (net (code "58") (name "Net-(Q11-A)") (class "Default")
      (node (ref "JP9") (pin "5") (pinfunction "5_5") (pintype "passive"))
      (node (ref "Q11") (pin "2") (pinfunction "A_2") (pintype "passive"))
      (node (ref "Q11") (pin "4") (pinfunction "TAB_4") (pintype "passive"))
      (node (ref "Q12") (pin "1") (pinfunction "K_1") (pintype "passive"))
      (node (ref "R112") (pin "2") (pinfunction "2_2") (pintype "passive"))
    )
    (net (code "59") (name "Net-(Q11-G)") (class "Default")
      (node (ref "Q11") (pin "3") (pinfunction "G_3") (pintype "passive"))
      (node (ref "U45") (pin "4") (pintype "passive"))
    )
    (net (code "60") (name "Net-(Q11-K)") (class "Default")
      (node (ref "JP9") (pin "6") (pinfunction "6_6") (pintype "passive"))
      (node (ref "Q11") (pin "1") (pinfunction "K_1") (pintype "passive"))
      (node (ref "Q12") (pin "2") (pinfunction "A_2") (pintype "passive"))
      (node (ref "Q12") (pin "4") (pinfunction "TAB_4") (pintype "passive"))
      (node (ref "R112") (pin "1") (pinfunction "1_1") (pintype "passive"))
    )
    (net (code "61") (name "Net-(Q12-G)") (class "Default")
      (node (ref "Q12") (pin "3") (pinfunction "G_3") (pintype "passive"))
      (node (ref "R111") (pin "2") (pinfunction "2_2") (pintype "passive"))
    )
    (net (code "62") (name "Net-(Q13-A)") (class "Default")
      (node (ref "JP9") (pin "3") (pinfunction "3_3") (pintype "passive"))
      (node (ref "Q13") (pin "2") (pinfunction "A_2") (pintype "passive"))
      (node (ref "Q13") (pin "4") (pinfunction "TAB_4") (pintype "passive"))
      (node (ref "Q14") (pin "1") (pinfunction "K_1") (pintype "passive"))
      (node (ref "R119") (pin "2") (pinfunction "2_2") (pintype "passive"))
    )
    (net (code "63") (name "Net-(Q13-G)") (class "Default")
      (node (ref "Q13") (pin "3") (pinfunction "G_3") (pintype "passive"))
      (node (ref "U48") (pin "4") (pintype "passive"))
    )
    (net (code "64") (name "Net-(Q13-K)") (class "Default")
      (node (ref "JP9") (pin "4") (pinfunction "4_4") (pintype "passive"))
      (node (ref "Q13") (pin "1") (pinfunction "K_1") (pintype "passive"))
      (node (ref "Q14") (pin "2") (pinfunction "A_2") (pintype "passive"))
      (node (ref "Q14") (pin "4") (pinfunction "TAB_4") (pintype "passive"))
      (node (ref "R119") (pin "1") (pinfunction "1_1") (pintype "passive"))
    )
    (net (code "65") (name "Net-(Q14-G)") (class "Default")
      (node (ref "Q14") (pin "3") (pinfunction "G_3") (pintype "passive"))
      (node (ref "R118") (pin "2") (pinfunction "2_2") (pintype "passive"))
    )
    (net (code "66") (name "Net-(Q15-A)") (class "Default")
      (node (ref "JP9") (pin "1") (pinfunction "1_1") (pintype "passive"))
      (node (ref "Q15") (pin "2") (pinfunction "A_2") (pintype "passive"))
      (node (ref "Q15") (pin "4") (pinfunction "TAB_4") (pintype "passive"))
      (node (ref "Q16") (pin "1") (pinfunction "K_1") (pintype "passive"))
      (node (ref "R122") (pin "2") (pinfunction "2_2") (pintype "passive"))
    )
    (net (code "67") (name "Net-(Q15-G)") (class "Default")
      (node (ref "Q15") (pin "3") (pinfunction "G_3") (pintype "passive"))
      (node (ref "U49") (pin "4") (pintype "passive"))
    )
    (net (code "68") (name "Net-(Q15-K)") (class "Default")
      (node (ref "JP9") (pin "2") (pinfunction "2_2") (pintype "passive"))
      (node (ref "Q15") (pin "1") (pinfunction "K_1") (pintype "passive"))
      (node (ref "Q16") (pin "2") (pinfunction "A_2") (pintype "passive"))
      (node (ref "Q16") (pin "4") (pinfunction "TAB_4") (pintype "passive"))
      (node (ref "R122") (pin "1") (pinfunction "1_1") (pintype "passive"))
    )
    (net (code "69") (name "Net-(Q16-G)") (class "Default")
      (node (ref "Q16") (pin "3") (pinfunction "G_3") (pintype "passive"))
      (node (ref "R121") (pin "2") (pinfunction "2_2") (pintype "passive"))
    )
    (net (code "70") (name "Net-(R105-Pad2)") (class "Default")
      (node (ref "R105") (pin "2") (pinfunction "2_2") (pintype "passive"))
      (node (ref "U42") (pin "1") (pintype "passive"))
    )
    (net (code "71") (name "Net-(R106-Pad1)") (class "Default")
      (node (ref "R106") (pin "1") (pinfunction "1_1") (pintype "passive"))
      (node (ref "U42") (pin "6") (pintype "passive"))
    )
    (net (code "72") (name "Net-(R110-Pad2)") (class "Default")
      (node (ref "R110") (pin "2") (pinfunction "2_2") (pintype "passive"))
      (node (ref "U45") (pin "1") (pintype "passive"))
    )
    (net (code "73") (name "Net-(R111-Pad1)") (class "Default")
      (node (ref "R111") (pin "1") (pinfunction "1_1") (pintype "passive"))
      (node (ref "U45") (pin "6") (pintype "passive"))
    )
    (net (code "74") (name "Net-(R117-Pad2)") (class "Default")
      (node (ref "R117") (pin "2") (pinfunction "2_2") (pintype "passive"))
      (node (ref "U48") (pin "1") (pintype "passive"))
    )
    (net (code "75") (name "Net-(R118-Pad1)") (class "Default")
      (node (ref "R118") (pin "1") (pinfunction "1_1") (pintype "passive"))
      (node (ref "U48") (pin "6") (pintype "passive"))
    )
    (net (code "76") (name "Net-(R120-Pad2)") (class "Default")
      (node (ref "R120") (pin "2") (pinfunction "2_2") (pintype "passive"))
      (node (ref "U49") (pin "1") (pintype "passive"))
    )
    (net (code "77") (name "Net-(R121-Pad1)") (class "Default")
      (node (ref "R121") (pin "1") (pinfunction "1_1") (pintype "passive"))
      (node (ref "U49") (pin "6") (pintype "passive"))
    )
    (net (code "78") (name "unconnected-(D7-A-Pad1)") (class "Default")
      (node (ref "D7") (pin "1") (pinfunction "A_1") (pintype "passive"))
    )
    (net (code "79") (name "unconnected-(D8-A-Pad1)") (class "Default")
      (node (ref "D8") (pin "1") (pinfunction "A_1") (pintype "passive"))
    )
    (net (code "80") (name "unconnected-(D10-A-Pad1)") (class "Default")
      (node (ref "D10") (pin "1") (pinfunction "A_1") (pintype "passive"))
    )
    (net (code "81") (name "unconnected-(D11-A-Pad1)") (class "Default")
      (node (ref "D11") (pin "1") (pinfunction "A_1") (pintype "passive"))
    )
    (net (code "82") (name "unconnected-(D13-A-Pad1)") (class "Default")
      (node (ref "D13") (pin "1") (pinfunction "A_1") (pintype "passive"))
    )
    (net (code "83") (name "unconnected-(D14-A-Pad1)") (class "Default")
      (node (ref "D14") (pin "1") (pinfunction "A_1") (pintype "passive"))
    )
    (net (code "84") (name "unconnected-(D15-A-Pad1)") (class "Default")
      (node (ref "D15") (pin "1") (pinfunction "A_1") (pintype "passive"))
    )
    (net (code "85") (name "unconnected-(D16-A-Pad1)") (class "Default")
      (node (ref "D16") (pin "1") (pinfunction "A_1") (pintype "passive"))
    )
  )
)
